# current_measure.net
KiCad netlist of a schematic drawn in EAGLE
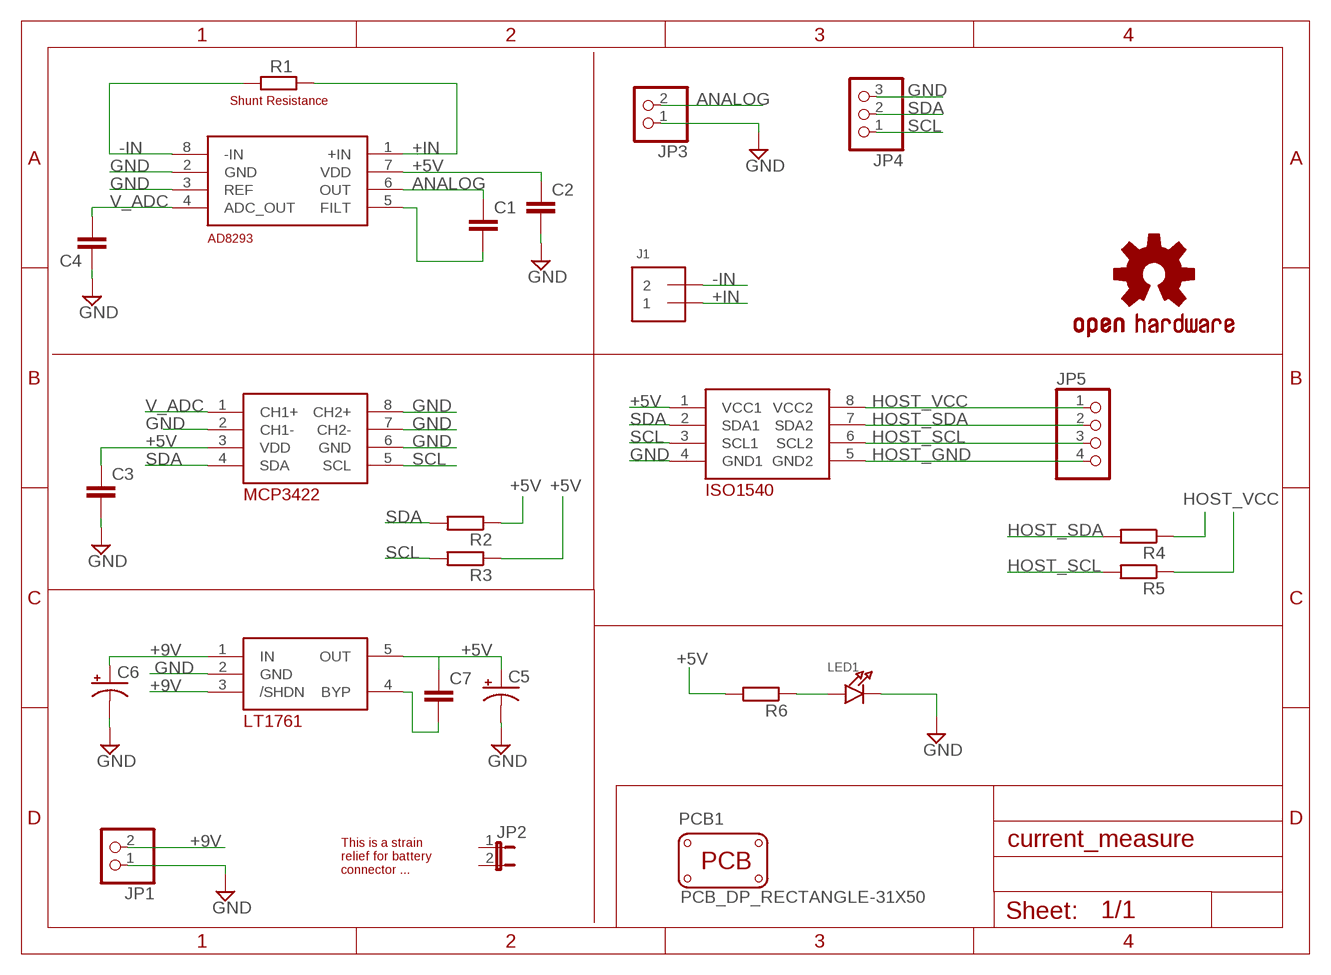
[diagram p0: schematic, sheet 1]

(export (version "E")
  (design (tool "Eeschema 10.0.6"))
  (components
    (comp (ref "C1")
      (value "C-EUC0603")
      (footprint "eagle-import:C0603")
      (libsource (lib "eagle-import") (part "C-EUC0603"))
    )
    (comp (ref "C2")
      (value "C-EUC0603")
      (footprint "eagle-import:C0603")
      (libsource (lib "eagle-import") (part "C-EUC0603"))
    )
    (comp (ref "C3")
      (value "C-EUC0603")
      (footprint "eagle-import:C0603")
      (libsource (lib "eagle-import") (part "C-EUC0603"))
    )
    (comp (ref "C4")
      (value "C-EUC0603")
      (footprint "eagle-import:C0603")
      (libsource (lib "eagle-import") (part "C-EUC0603"))
    )
    (comp (ref "C5")
      (value "CPOL-USC/6032-28R")
      (footprint "eagle-import:C_6032-28R")
      (libsource (lib "eagle-import") (part "CPOL-USC/6032-28R"))
    )
    (comp (ref "C6")
      (value "CPOL-USC/6032-28R")
      (footprint "eagle-import:C_6032-28R")
      (libsource (lib "eagle-import") (part "CPOL-USC/6032-28R"))
    )
    (comp (ref "C7")
      (value "C-EUC0603")
      (footprint "eagle-import:C0603")
      (libsource (lib "eagle-import") (part "C-EUC0603"))
    )
    (comp (ref "J1")
      (value "TERMBLOCK_1X2")
      (footprint "eagle-import:TERMBLOCK_1X2-3.5MM")
      (libsource (lib "eagle-import") (part "TERMBLOCK_1X2"))
    )
    (comp (ref "JP1")
      (value "PINHD-1X2")
      (footprint "eagle-import:1X02")
      (libsource (lib "eagle-import") (part "PINHD-1X2"))
    )
    (comp (ref "JP2")
      (value "JUMPER2")
      (footprint "eagle-import:JUMPER2")
      (libsource (lib "eagle-import") (part "JUMPER2"))
    )
    (comp (ref "JP3")
      (value "PINHD-1X2")
      (footprint "eagle-import:1X02")
      (libsource (lib "eagle-import") (part "PINHD-1X2"))
    )
    (comp (ref "JP4")
      (value "HEADER-1X3ROUND")
      (footprint "eagle-import:1X03_ROUND")
      (libsource (lib "eagle-import") (part "HEADER-1X3ROUND"))
    )
    (comp (ref "JP5")
      (value "HEADER-1X4ROUND")
      (footprint "eagle-import:1X04_ROUND")
      (libsource (lib "eagle-import") (part "HEADER-1X4ROUND"))
    )
    (comp (ref "LED1")
      (value "LED0805_NOOUTLINE")
      (footprint "eagle-import:CHIPLED_0805_NOOUTLINE")
      (libsource (lib "eagle-import") (part "LED0805_NOOUTLINE"))
    )
    (comp (ref "LOGO1")
      (value "OSHW-LOGOM")
      (footprint "eagle-import:OSHW-LOGO-M")
      (libsource (lib "eagle-import") (part "OSHW-LOGOM"))
    )
    (comp (ref "PCB1")
      (value "PCB_DP_RECTANGLE-31X50")
      (footprint "eagle-import:DP5031_V1")
      (libsource (lib "eagle-import") (part "PCB_DP_RECTANGLE-31X50"))
    )
    (comp (ref "R1")
      (value "R-EU_R1206")
      (footprint "eagle-import:R1206")
      (libsource (lib "eagle-import") (part "R-EU_R1206"))
    )
    (comp (ref "R2")
      (value "R-EU_R0603")
      (footprint "eagle-import:R0603")
      (libsource (lib "eagle-import") (part "R-EU_R0603"))
    )
    (comp (ref "R3")
      (value "R-EU_R0603")
      (footprint "eagle-import:R0603")
      (libsource (lib "eagle-import") (part "R-EU_R0603"))
    )
    (comp (ref "R4")
      (value "R-EU_R0603")
      (footprint "eagle-import:R0603")
      (libsource (lib "eagle-import") (part "R-EU_R0603"))
    )
    (comp (ref "R5")
      (value "R-EU_R0603")
      (footprint "eagle-import:R0603")
      (libsource (lib "eagle-import") (part "R-EU_R0603"))
    )
    (comp (ref "R6")
      (value "R-EU_R0603")
      (footprint "eagle-import:R0603")
      (libsource (lib "eagle-import") (part "R-EU_R0603"))
    )
    (comp (ref "U$1")
      (value "IHSAN_AD8293")
      (footprint "eagle-import:SOT23-8")
      (libsource (lib "eagle-import") (part "IHSAN_AD8293"))
    )
    (comp (ref "U$2")
      (value "IHSAN_MCP3422")
      (footprint "eagle-import:SO08")
      (libsource (lib "eagle-import") (part "IHSAN_MCP3422"))
    )
    (comp (ref "U$3")
      (value "IHSAN_LT1761")
      (footprint "eagle-import:SOT23-5")
      (libsource (lib "eagle-import") (part "IHSAN_LT1761"))
    )
    (comp (ref "U$4")
      (value "IHSAN_ISO1540")
      (footprint "eagle-import:SO08")
      (libsource (lib "eagle-import") (part "IHSAN_ISO1540"))
    )
  )
  (nets
    (net (code "1") (name "/+5V") (class "Default")
      (node (ref "C2") (pin "1") (pinfunction "1_1") (pintype "passive"))
      (node (ref "C3") (pin "1") (pinfunction "1_1") (pintype "passive"))
      (node (ref "C5") (pin "+") (pinfunction "+_+") (pintype "passive"))
      (node (ref "C7") (pin "1") (pinfunction "1_1") (pintype "passive"))
      (node (ref "R2") (pin "1") (pinfunction "1_1") (pintype "passive"))
      (node (ref "R3") (pin "1") (pinfunction "1_1") (pintype "passive"))
      (node (ref "R6") (pin "2") (pinfunction "2_2") (pintype "passive"))
      (node (ref "U$1") (pin "7") (pinfunction "VDD_7") (pintype "bidirectional"))
      (node (ref "U$2") (pin "3") (pinfunction "VDD_3") (pintype "bidirectional"))
      (node (ref "U$3") (pin "5") (pinfunction "OUT_5") (pintype "bidirectional"))
      (node (ref "U$4") (pin "1") (pinfunction "VCC1_1") (pintype "bidirectional"))
    )
    (net (code "2") (name "/+9V") (class "Default")
      (node (ref "C6") (pin "+") (pinfunction "+_+") (pintype "passive"))
      (node (ref "JP1") (pin "2") (pinfunction "2_2") (pintype "passive"))
      (node (ref "U$3") (pin "1") (pinfunction "IN_1") (pintype "bidirectional"))
      (node (ref "U$3") (pin "3") (pinfunction "/SHDN_3") (pintype "bidirectional"))
    )
    (net (code "3") (name "/+IN") (class "Default")
      (node (ref "J1") (pin "1") (pinfunction "1_1") (pintype "passive"))
      (node (ref "R1") (pin "2") (pinfunction "2_2") (pintype "passive"))
      (node (ref "U$1") (pin "1") (pinfunction "+IN_1") (pintype "bidirectional"))
    )
    (net (code "4") (name "/-IN") (class "Default")
      (node (ref "J1") (pin "2") (pinfunction "2_2") (pintype "passive"))
      (node (ref "R1") (pin "1") (pinfunction "1_1") (pintype "passive"))
      (node (ref "U$1") (pin "8") (pinfunction "-IN_8") (pintype "bidirectional"))
    )
    (net (code "5") (name "/ANALOG") (class "Default")
      (node (ref "C1") (pin "1") (pinfunction "1_1") (pintype "passive"))
      (node (ref "JP3") (pin "2") (pinfunction "2_2") (pintype "passive"))
      (node (ref "U$1") (pin "6") (pinfunction "OUT_6") (pintype "bidirectional"))
    )
    (net (code "6") (name "/HOST_GND") (class "Default")
      (node (ref "JP5") (pin "4") (pinfunction "4_4") (pintype "passive"))
      (node (ref "U$4") (pin "5") (pinfunction "GND2_5") (pintype "bidirectional"))
    )
    (net (code "7") (name "/HOST_SCL") (class "Default")
      (node (ref "JP5") (pin "3") (pinfunction "3_3") (pintype "passive"))
      (node (ref "R5") (pin "2") (pinfunction "2_2") (pintype "passive"))
      (node (ref "U$4") (pin "6") (pinfunction "SCL2_6") (pintype "bidirectional"))
    )
    (net (code "8") (name "/HOST_SDA") (class "Default")
      (node (ref "JP5") (pin "2") (pinfunction "2_2") (pintype "passive"))
      (node (ref "R4") (pin "2") (pinfunction "2_2") (pintype "passive"))
      (node (ref "U$4") (pin "7") (pinfunction "SDA2_7") (pintype "bidirectional"))
    )
    (net (code "9") (name "/HOST_VCC") (class "Default")
      (node (ref "JP5") (pin "1") (pinfunction "1_1") (pintype "passive"))
      (node (ref "R4") (pin "1") (pinfunction "1_1") (pintype "passive"))
      (node (ref "R5") (pin "1") (pinfunction "1_1") (pintype "passive"))
      (node (ref "U$4") (pin "8") (pinfunction "VCC2_8") (pintype "bidirectional"))
    )
    (net (code "10") (name "/SCL") (class "Default")
      (node (ref "JP4") (pin "1") (pinfunction "1_1") (pintype "passive"))
      (node (ref "R3") (pin "2") (pinfunction "2_2") (pintype "passive"))
      (node (ref "U$2") (pin "5") (pinfunction "SCL_5") (pintype "bidirectional"))
      (node (ref "U$4") (pin "3") (pinfunction "SCL1_3") (pintype "bidirectional"))
    )
    (net (code "11") (name "/SDA") (class "Default")
      (node (ref "JP4") (pin "2") (pinfunction "2_2") (pintype "passive"))
      (node (ref "R2") (pin "2") (pinfunction "2_2") (pintype "passive"))
      (node (ref "U$2") (pin "4") (pinfunction "SDA_4") (pintype "bidirectional"))
      (node (ref "U$4") (pin "2") (pinfunction "SDA1_2") (pintype "bidirectional"))
    )
    (net (code "12") (name "/V_ADC") (class "Default")
      (node (ref "C4") (pin "2") (pinfunction "2_2") (pintype "passive"))
      (node (ref "U$1") (pin "4") (pinfunction "ADC_OUT_4") (pintype "bidirectional"))
      (node (ref "U$2") (pin "1") (pinfunction "CH1+_1") (pintype "bidirectional"))
    )
    (net (code "13") (name "GND") (class "Default")
      (node (ref "C2") (pin "2") (pinfunction "2_2") (pintype "passive"))
      (node (ref "C3") (pin "2") (pinfunction "2_2") (pintype "passive"))
      (node (ref "C4") (pin "1") (pinfunction "1_1") (pintype "passive"))
      (node (ref "C5") (pin "-") (pinfunction "-_-") (pintype "passive"))
      (node (ref "C6") (pin "-") (pinfunction "-_-") (pintype "passive"))
      (node (ref "JP1") (pin "1") (pinfunction "1_1") (pintype "passive"))
      (node (ref "JP3") (pin "1") (pinfunction "1_1") (pintype "passive"))
      (node (ref "JP4") (pin "3") (pinfunction "3_3") (pintype "passive"))
      (node (ref "LED1") (pin "C") (pinfunction "C_C") (pintype "passive"))
      (node (ref "U$1") (pin "2") (pinfunction "GND_2") (pintype "bidirectional"))
      (node (ref "U$1") (pin "3") (pinfunction "REF_3") (pintype "bidirectional"))
      (node (ref "U$2") (pin "2") (pinfunction "CH1-_2") (pintype "bidirectional"))
      (node (ref "U$2") (pin "6") (pinfunction "GND_6") (pintype "bidirectional"))
      (node (ref "U$2") (pin "7") (pinfunction "CH2-_7") (pintype "bidirectional"))
      (node (ref "U$2") (pin "8") (pinfunction "CH2+_8") (pintype "bidirectional"))
      (node (ref "U$3") (pin "2") (pinfunction "GND_2") (pintype "bidirectional"))
      (node (ref "U$4") (pin "4") (pinfunction "GND1_4") (pintype "bidirectional"))
    )
    (net (code "14") (name "Net-(LED1-PadA)") (class "Default")
      (node (ref "LED1") (pin "A") (pinfunction "A_A") (pintype "passive"))
      (node (ref "R6") (pin "1") (pinfunction "1_1") (pintype "passive"))
    )
    (net (code "15") (name "Net-(U$1-FILT)") (class "Default")
      (node (ref "C1") (pin "2") (pinfunction "2_2") (pintype "passive"))
      (node (ref "U$1") (pin "5") (pinfunction "FILT_5") (pintype "bidirectional"))
    )
    (net (code "16") (name "Net-(U$3-BYP)") (class "Default")
      (node (ref "C7") (pin "2") (pinfunction "2_2") (pintype "passive"))
      (node (ref "U$3") (pin "4") (pinfunction "BYP_4") (pintype "bidirectional"))
    )
    (net (code "17") (name "unconnected-(JP2-Pad1)") (class "Default")
      (node (ref "JP2") (pin "1") (pinfunction "1_1") (pintype "passive"))
    )
    (net (code "18") (name "unconnected-(JP2-Pad2)") (class "Default")
      (node (ref "JP2") (pin "2") (pinfunction "2_2") (pintype "passive"))
    )
  )
)
